# ALLPRINT-CAPBOARD-677512-MCU.net
KiCad netlist of a schematic drawn in Altium Designer
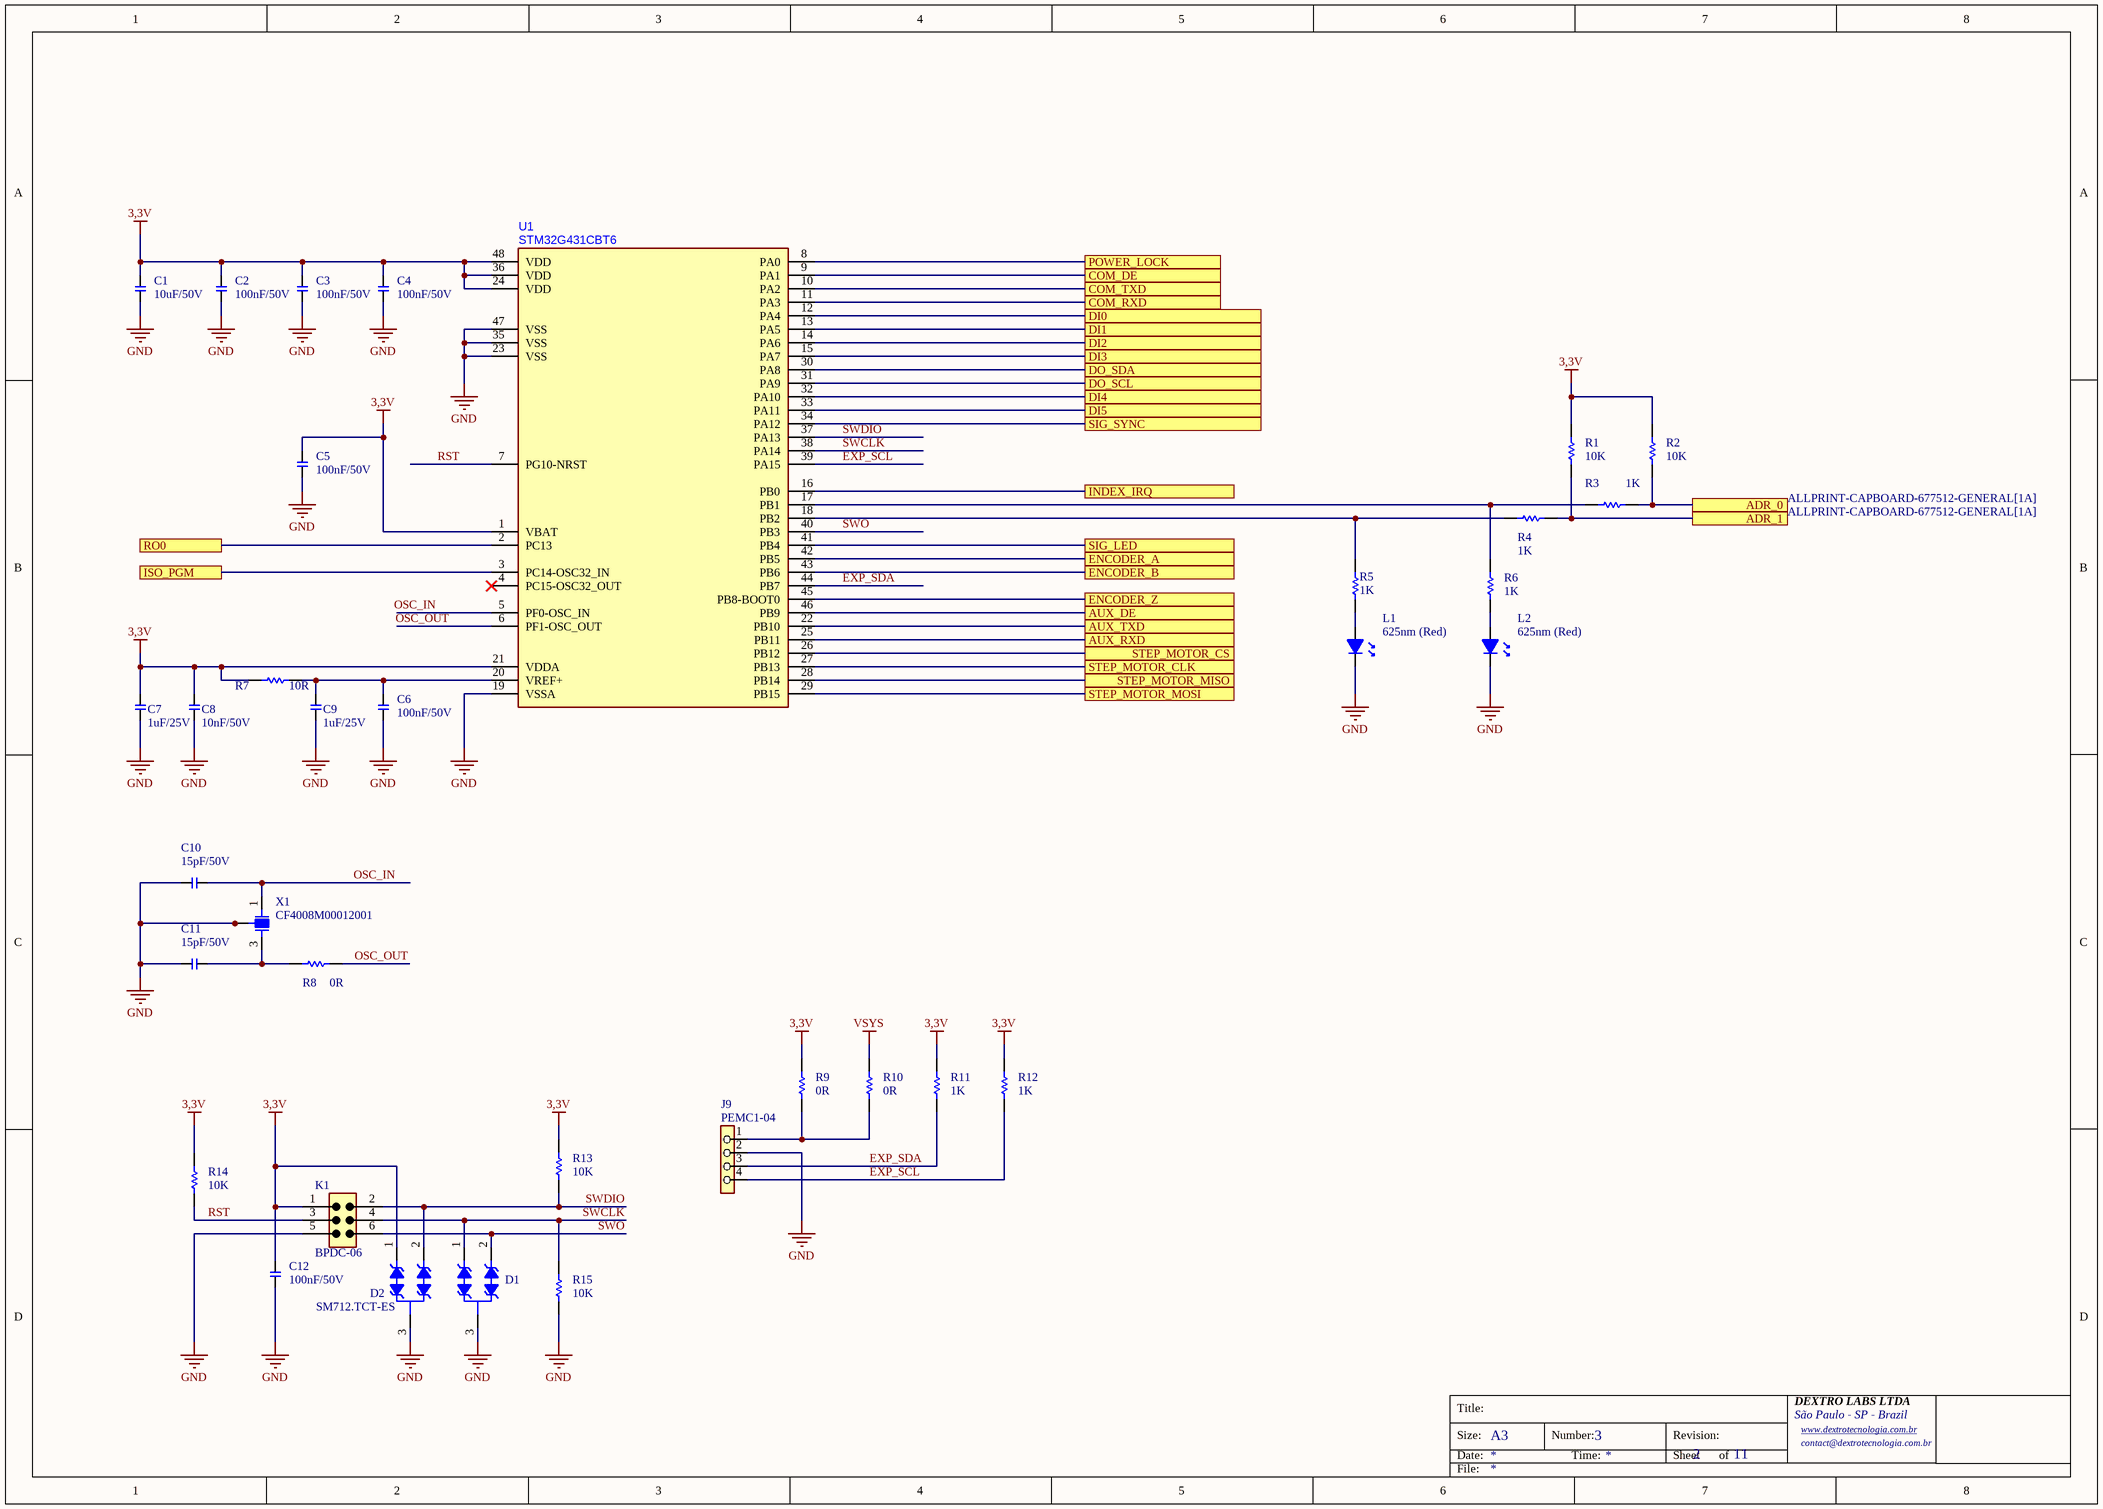
[diagram p0: ALLPRINT-CAPBOARD-677512-MCU.SchDoc]

(export (version "E")
  (design (tool "Eeschema 10.0.6"))
  (components
    (comp (ref "C1")
      (value "10uF/50V")
      (footprint "CAP-0805")
      (description "50V 10uF X5R ±10% 1206 Multilayer Ceramic Capacitors MLCC - SMD/SMT ROHS")
      (libsource (lib "dextro-labs") (part "CAP-10uF/50V-0805-X5R-MLCC"))
    )
    (comp (ref "C2")
      (value "100nF/50V")
      (footprint "CAP-0603")
      (description "50V 100nF X7R ±10% 0603 Multilayer Ceramic Capacitors MLCC - SMD/SMT ROHS")
      (libsource (lib "dextro-labs") (part "CAP-100nF/50V-0603-X7R-MLCC"))
    )
    (comp (ref "C3")
      (value "100nF/50V")
      (footprint "CAP-0603")
      (description "50V 100nF X7R ±10% 0603 Multilayer Ceramic Capacitors MLCC - SMD/SMT ROHS")
      (libsource (lib "dextro-labs") (part "CAP-100nF/50V-0603-X7R-MLCC"))
    )
    (comp (ref "C4")
      (value "100nF/50V")
      (footprint "CAP-0603")
      (description "50V 100nF X7R ±10% 0603 Multilayer Ceramic Capacitors MLCC - SMD/SMT ROHS")
      (libsource (lib "dextro-labs") (part "CAP-100nF/50V-0603-X7R-MLCC"))
    )
    (comp (ref "C5")
      (value "100nF/50V")
      (footprint "CAP-0603")
      (description "50V 100nF X7R ±10% 0603 Multilayer Ceramic Capacitors MLCC - SMD/SMT ROHS")
      (libsource (lib "dextro-labs") (part "CAP-100nF/50V-0603-X7R-MLCC"))
    )
    (comp (ref "C6")
      (value "100nF/50V")
      (footprint "CAP-0603")
      (description "50V 100nF X7R ±10% 0603 Multilayer Ceramic Capacitors MLCC - SMD/SMT ROHS")
      (libsource (lib "dextro-labs") (part "CAP-100nF/50V-0603-X7R-MLCC"))
    )
    (comp (ref "C7")
      (value "1uF/25V")
      (footprint "CAP-0603")
      (description "25V 1uF X7R ±10% 0603 Multilayer Ceramic Capacitors MLCC - SMD/SMT ROHS")
      (libsource (lib "dextro-labs") (part "CAP-1uF/25V-0603-X7R-MLCC"))
    )
    (comp (ref "C8")
      (value "10nF/50V")
      (footprint "CAP-0603")
      (description "50V 10nF X7R ±10% 0603 Multilayer Ceramic Capacitors MLCC - SMD/SMT ROHS")
      (libsource (lib "dextro-labs") (part "CAP-10nF/50V-0603-X7R-MLCC"))
    )
    (comp (ref "C9")
      (value "1uF/25V")
      (footprint "CAP-0603")
      (description "25V 1uF X7R ±10% 0603 Multilayer Ceramic Capacitors MLCC - SMD/SMT ROHS")
      (libsource (lib "dextro-labs") (part "CAP-1uF/25V-0603-X7R-MLCC"))
    )
    (comp (ref "C10")
      (value "15pF/50V")
      (footprint "CAP-0603")
      (description "50V 15pF NP0 ±5% 0603 Ceramic Capacitors RoHS")
      (libsource (lib "dextro-labs") (part "CAP-15pF/50V-0603-NP0-MLCC"))
    )
    (comp (ref "C11")
      (value "15pF/50V")
      (footprint "CAP-0603")
      (description "50V 15pF NP0 ±5% 0603 Ceramic Capacitors RoHS")
      (libsource (lib "dextro-labs") (part "CAP-15pF/50V-0603-NP0-MLCC"))
    )
    (comp (ref "C12")
      (value "100nF/50V")
      (footprint "CAP-0603")
      (description "50V 100nF X7R ±10% 0603 Multilayer Ceramic Capacitors MLCC - SMD/SMT ROHS")
      (libsource (lib "dextro-labs") (part "CAP-100nF/50V-0603-X7R-MLCC"))
    )
    (comp (ref "D1")
      (value "SM712.TCT-ES")
      (footprint "SOT23-3")
      (description "400W@8/20us Bidirectional SOT-23 ESD and Surge Protection (TVS/ESD) ROHS")
      (libsource (lib "dextro-labs") (part "SM712.TCT-ES"))
    )
    (comp (ref "D2")
      (value "SM712.TCT-ES")
      (footprint "SOT23-3")
      (description "400W@8/20us Bidirectional SOT-23 ESD and Surge Protection (TVS/ESD) ROHS")
      (libsource (lib "dextro-labs") (part "SM712.TCT-ES"))
    )
    (comp (ref "J9")
      (value "PEMC1-04")
      (footprint "PEMC1-04")
      (description "CONECTOR PASSO 2,5mm\r\n250VCA\r\n3A\r\n10mOHMS")
      (libsource (lib "dextro-labs") (part "PEMC1-04"))
    )
    (comp (ref "K1")
      (value "BPDC-06")
      (footprint "BPDC-06")
      (description "BARRA DE PINOS DUPLA 2,54mm 6 VIAS 180º")
      (libsource (lib "dextro-labs") (part "BPDC-06"))
    )
    (comp (ref "L1")
      (value "YLED0603R")
      (footprint "LED-SMD-0603")
      (description "25mA 120mcd 620nm~625nm Red 1.8V~2.4V 0603 LED Indication - Discrete RoHS")
      (fields (field (name "WAVELENGTH") "625nm (Red)"))
      (libsource (lib "dextro-labs") (part "D-LED-SMD-PKG@0603-RED"))
    )
    (comp (ref "L2")
      (value "YLED0603R")
      (footprint "LED-SMD-0603")
      (description "25mA 120mcd 620nm~625nm Red 1.8V~2.4V 0603 LED Indication - Discrete RoHS")
      (fields (field (name "WAVELENGTH") "625nm (Red)"))
      (libsource (lib "dextro-labs") (part "D-LED-SMD-PKG@0603-RED"))
    )
    (comp (ref "R1")
      (value "10K")
      (footprint "RES-0603")
      (description "100mW Thick Film Resistor 75V ±100ppm/℃ ±1% 10kΩ 0603 Chip Resistor - Surface Mount ROHS")
      (libsource (lib "dextro-labs") (part "RES-10K-1%-100mW-0603"))
    )
    (comp (ref "R2")
      (value "10K")
      (footprint "RES-0603")
      (description "100mW Thick Film Resistor 75V ±100ppm/℃ ±1% 10kΩ 0603 Chip Resistor - Surface Mount ROHS")
      (libsource (lib "dextro-labs") (part "RES-10K-1%-100mW-0603"))
    )
    (comp (ref "R3")
      (value "1K")
      (footprint "RES-0603")
      (description "100mW Thick Film Resistor 75V ±100ppm/℃ ±1% 1kΩ 0603 Chip Resistor - Surface Mount ROHS")
      (libsource (lib "dextro-labs") (part "RES-1K-1%-100mW-0603"))
    )
    (comp (ref "R4")
      (value "1K")
      (footprint "RES-0603")
      (description "100mW Thick Film Resistor 75V ±100ppm/℃ ±1% 1kΩ 0603 Chip Resistor - Surface Mount ROHS")
      (libsource (lib "dextro-labs") (part "RES-1K-1%-100mW-0603"))
    )
    (comp (ref "R5")
      (value "1K")
      (footprint "RES-0603")
      (description "100mW Thick Film Resistor 75V ±100ppm/℃ ±1% 1kΩ 0603 Chip Resistor - Surface Mount ROHS")
      (libsource (lib "dextro-labs") (part "RES-1K-1%-100mW-0603"))
    )
    (comp (ref "R6")
      (value "1K")
      (footprint "RES-0603")
      (description "100mW Thick Film Resistor 75V ±100ppm/℃ ±1% 1kΩ 0603 Chip Resistor - Surface Mount ROHS")
      (libsource (lib "dextro-labs") (part "RES-1K-1%-100mW-0603"))
    )
    (comp (ref "R7")
      (value "10R")
      (footprint "RES-0603")
      (description "100mW Thick Film Resistor 75V ±1% ±400ppm/℃ 10Ω 0603 Chip Resistor - Surface Mount ROHS")
      (libsource (lib "dextro-labs") (part "RES-10R-1%-100mW-0603"))
    )
    (comp (ref "R8")
      (value "0R")
      (footprint "RES-0603")
      (description "100mW 0Ω 75V Thick Film Resistor ±5% 0603 Chip Resistor - Surface Mount RoHS")
      (libsource (lib "dextro-labs") (part "RES-0R-1%-100mW-0603"))
    )
    (comp (ref "R9")
      (value "0R")
      (footprint "RES-0805")
      (description "100mW Thick Film Resistor 75V ±100ppm/℃ ±1% 0R Chip Resistor - Surface Mount ROHS")
      (libsource (lib "dextro-labs") (part "RES-0R-1%-125mW-0805"))
    )
    (comp (ref "R10")
      (value "0R")
      (footprint "RES-0805")
      (description "100mW Thick Film Resistor 75V ±100ppm/℃ ±1% 0R Chip Resistor - Surface Mount ROHS")
      (libsource (lib "dextro-labs") (part "RES-0R-1%-125mW-0805"))
    )
    (comp (ref "R11")
      (value "1K")
      (footprint "RES-0603")
      (description "100mW Thick Film Resistor 75V ±100ppm/℃ ±1% 1kΩ 0603 Chip Resistor - Surface Mount ROHS")
      (libsource (lib "dextro-labs") (part "RES-1K-1%-100mW-0603"))
    )
    (comp (ref "R12")
      (value "1K")
      (footprint "RES-0603")
      (description "100mW Thick Film Resistor 75V ±100ppm/℃ ±1% 1kΩ 0603 Chip Resistor - Surface Mount ROHS")
      (libsource (lib "dextro-labs") (part "RES-1K-1%-100mW-0603"))
    )
    (comp (ref "R13")
      (value "10K")
      (footprint "RES-0603")
      (description "100mW Thick Film Resistor 75V ±100ppm/℃ ±1% 10kΩ 0603 Chip Resistor - Surface Mount ROHS")
      (libsource (lib "dextro-labs") (part "RES-10K-1%-100mW-0603"))
    )
    (comp (ref "R14")
      (value "10K")
      (footprint "RES-0603")
      (description "100mW Thick Film Resistor 75V ±100ppm/℃ ±1% 10kΩ 0603 Chip Resistor - Surface Mount ROHS")
      (libsource (lib "dextro-labs") (part "RES-10K-1%-100mW-0603"))
    )
    (comp (ref "R15")
      (value "10K")
      (footprint "RES-0603")
      (description "100mW Thick Film Resistor 75V ±100ppm/℃ ±1% 10kΩ 0603 Chip Resistor - Surface Mount ROHS")
      (libsource (lib "dextro-labs") (part "RES-10K-1%-100mW-0603"))
    )
    (comp (ref "U1")
      (value "STM32G431CBT6")
      (footprint "LQFP-48_L7.0-W7.0-P0.50-LS9.0-BL")
      (fields (field (name "MANUFACTURER") "ST(意法半导体)"))
      (libsource (lib "dextro-labs") (part "STM32G431CBT6"))
    )
    (comp (ref "X1")
      (value "CF4008M00012001")
      (footprint "TAXM8M4RDBCCT2T")
      (description "Crystal Oscillator 12pF SMD3225-4P Crystals RoHS")
      (libsource (lib "dextro-labs") (part "XTAL-8MHZ-3225-SMD"))
    )
  )
  (nets
    (net (code "1") (name "/ADR_0") (class "Default")
      (node (ref "R2") (pin "1") (pinfunction "1_1") (pintype "passive"))
      (node (ref "R3") (pin "2") (pinfunction "2_2") (pintype "passive"))
    )
    (net (code "2") (name "/ADR_1") (class "Default")
      (node (ref "R1") (pin "1") (pinfunction "1_1") (pintype "passive"))
      (node (ref "R4") (pin "2") (pinfunction "2_2") (pintype "passive"))
    )
    (net (code "3") (name "/AUX_DE") (class "Default")
      (node (ref "U1") (pin "46") (pinfunction "PB9_46") (pintype "passive"))
    )
    (net (code "4") (name "/AUX_RXD") (class "Default")
      (node (ref "U1") (pin "25") (pinfunction "PB11_25") (pintype "passive"))
    )
    (net (code "5") (name "/AUX_TXD") (class "Default")
      (node (ref "U1") (pin "22") (pinfunction "PB10_22") (pintype "passive"))
    )
    (net (code "6") (name "/COM_DE") (class "Default")
      (node (ref "U1") (pin "9") (pinfunction "PA1_9") (pintype "passive"))
    )
    (net (code "7") (name "/COM_RXD") (class "Default")
      (node (ref "U1") (pin "11") (pinfunction "PA3_11") (pintype "passive"))
    )
    (net (code "8") (name "/COM_TXD") (class "Default")
      (node (ref "U1") (pin "10") (pinfunction "PA2_10") (pintype "passive"))
    )
    (net (code "9") (name "/DI0") (class "Default")
      (node (ref "U1") (pin "12") (pinfunction "PA4_12") (pintype "passive"))
    )
    (net (code "10") (name "/DI1") (class "Default")
      (node (ref "U1") (pin "13") (pinfunction "PA5_13") (pintype "passive"))
    )
    (net (code "11") (name "/DI2") (class "Default")
      (node (ref "U1") (pin "14") (pinfunction "PA6_14") (pintype "passive"))
    )
    (net (code "12") (name "/DI3") (class "Default")
      (node (ref "U1") (pin "15") (pinfunction "PA7_15") (pintype "passive"))
    )
    (net (code "13") (name "/DI4") (class "Default")
      (node (ref "U1") (pin "32") (pinfunction "PA10_32") (pintype "passive"))
    )
    (net (code "14") (name "/DI5") (class "Default")
      (node (ref "U1") (pin "33") (pinfunction "PA11_33") (pintype "passive"))
    )
    (net (code "15") (name "/DO_SCL") (class "Default")
      (node (ref "U1") (pin "31") (pinfunction "PA9_31") (pintype "passive"))
    )
    (net (code "16") (name "/DO_SDA") (class "Default")
      (node (ref "U1") (pin "30") (pinfunction "PA8_30") (pintype "passive"))
    )
    (net (code "17") (name "/ENCODER_A") (class "Default")
      (node (ref "U1") (pin "42") (pinfunction "PB5_42") (pintype "passive"))
    )
    (net (code "18") (name "/ENCODER_B") (class "Default")
      (node (ref "U1") (pin "43") (pinfunction "PB6_43") (pintype "passive"))
    )
    (net (code "19") (name "/ENCODER_Z") (class "Default")
      (node (ref "U1") (pin "45") (pinfunction "PB8-BOOT0_45") (pintype "passive"))
    )
    (net (code "20") (name "/EXP_SCL") (class "Default")
      (node (ref "J9") (pin "4") (pinfunction "4_4") (pintype "passive"))
      (node (ref "R12") (pin "1") (pinfunction "1_1") (pintype "passive"))
      (node (ref "U1") (pin "39") (pinfunction "PA15_39") (pintype "passive"))
    )
    (net (code "21") (name "/EXP_SDA") (class "Default")
      (node (ref "J9") (pin "3") (pinfunction "3_3") (pintype "passive"))
      (node (ref "R11") (pin "1") (pinfunction "1_1") (pintype "passive"))
      (node (ref "U1") (pin "44") (pinfunction "PB7_44") (pintype "passive"))
    )
    (net (code "22") (name "/INDEX_IRQ") (class "Default")
      (node (ref "U1") (pin "16") (pinfunction "PB0_16") (pintype "passive"))
    )
    (net (code "23") (name "/ISO_PGM") (class "Default")
      (node (ref "U1") (pin "3") (pinfunction "PC14-OSC32_IN_3") (pintype "passive"))
    )
    (net (code "24") (name "/OSC_IN") (class "Default")
      (node (ref "C10") (pin "2") (pinfunction "2_2") (pintype "passive"))
      (node (ref "U1") (pin "5") (pinfunction "PF0-OSC_IN_5") (pintype "passive"))
      (node (ref "X1") (pin "1") (pinfunction "1_1") (pintype "passive"))
    )
    (net (code "25") (name "/OSC_OUT") (class "Default")
      (node (ref "R8") (pin "2") (pinfunction "2_2") (pintype "passive"))
      (node (ref "U1") (pin "6") (pinfunction "PF1-OSC_OUT_6") (pintype "passive"))
    )
    (net (code "26") (name "/POWER_LOCK") (class "Default")
      (node (ref "U1") (pin "8") (pinfunction "PA0_8") (pintype "passive"))
    )
    (net (code "27") (name "/RO0") (class "Default")
      (node (ref "U1") (pin "2") (pinfunction "PC13_2") (pintype "passive"))
    )
    (net (code "28") (name "/RST") (class "Default")
      (node (ref "K1") (pin "3") (pinfunction "3_3") (pintype "passive"))
      (node (ref "R14") (pin "1") (pinfunction "1_1") (pintype "passive"))
      (node (ref "U1") (pin "7") (pinfunction "PG10-NRST_7") (pintype "passive"))
    )
    (net (code "29") (name "/SIG_LED") (class "Default")
      (node (ref "U1") (pin "41") (pinfunction "PB4_41") (pintype "passive"))
    )
    (net (code "30") (name "/SIG_SYNC") (class "Default")
      (node (ref "U1") (pin "34") (pinfunction "PA12_34") (pintype "passive"))
    )
    (net (code "31") (name "/STEP_MOTOR_CLK") (class "Default")
      (node (ref "U1") (pin "27") (pinfunction "PB13_27") (pintype "passive"))
    )
    (net (code "32") (name "/STEP_MOTOR_CS") (class "Default")
      (node (ref "U1") (pin "26") (pinfunction "PB12_26") (pintype "passive"))
    )
    (net (code "33") (name "/STEP_MOTOR_MISO") (class "Default")
      (node (ref "U1") (pin "28") (pinfunction "PB14_28") (pintype "passive"))
    )
    (net (code "34") (name "/STEP_MOTOR_MOSI") (class "Default")
      (node (ref "U1") (pin "29") (pinfunction "PB15_29") (pintype "passive"))
    )
    (net (code "35") (name "/SWCLK") (class "Default")
      (node (ref "D1") (pin "1") (pinfunction "A1_1") (pintype "passive"))
      (node (ref "K1") (pin "4") (pinfunction "4_4") (pintype "passive"))
      (node (ref "R15") (pin "2") (pinfunction "2_2") (pintype "passive"))
      (node (ref "U1") (pin "38") (pinfunction "PA14_38") (pintype "passive"))
    )
    (net (code "36") (name "/SWDIO") (class "Default")
      (node (ref "D2") (pin "2") (pinfunction "A2_2") (pintype "passive"))
      (node (ref "K1") (pin "2") (pinfunction "2_2") (pintype "passive"))
      (node (ref "R13") (pin "1") (pinfunction "1_1") (pintype "passive"))
      (node (ref "U1") (pin "37") (pinfunction "PA13_37") (pintype "passive"))
    )
    (net (code "37") (name "/SWO") (class "Default")
      (node (ref "D1") (pin "2") (pinfunction "A2_2") (pintype "passive"))
      (node (ref "K1") (pin "6") (pinfunction "6_6") (pintype "passive"))
      (node (ref "U1") (pin "40") (pinfunction "PB3_40") (pintype "passive"))
    )
    (net (code "38") (name "3,3V") (class "Default")
      (node (ref "C1") (pin "2") (pinfunction "2_2") (pintype "passive"))
      (node (ref "C12") (pin "2") (pinfunction "2_2") (pintype "passive"))
      (node (ref "C2") (pin "2") (pinfunction "2_2") (pintype "passive"))
      (node (ref "C3") (pin "2") (pinfunction "2_2") (pintype "passive"))
      (node (ref "C4") (pin "2") (pinfunction "2_2") (pintype "passive"))
      (node (ref "C5") (pin "2") (pinfunction "2_2") (pintype "passive"))
      (node (ref "C7") (pin "2") (pinfunction "2_2") (pintype "passive"))
      (node (ref "C8") (pin "2") (pinfunction "2_2") (pintype "passive"))
      (node (ref "D2") (pin "1") (pinfunction "A1_1") (pintype "passive"))
      (node (ref "K1") (pin "1") (pinfunction "1_1") (pintype "passive"))
      (node (ref "R1") (pin "2") (pinfunction "2_2") (pintype "passive"))
      (node (ref "R11") (pin "2") (pinfunction "2_2") (pintype "passive"))
      (node (ref "R12") (pin "2") (pinfunction "2_2") (pintype "passive"))
      (node (ref "R13") (pin "2") (pinfunction "2_2") (pintype "passive"))
      (node (ref "R14") (pin "2") (pinfunction "2_2") (pintype "passive"))
      (node (ref "R2") (pin "2") (pinfunction "2_2") (pintype "passive"))
      (node (ref "R7") (pin "1") (pinfunction "1_1") (pintype "passive"))
      (node (ref "R9") (pin "2") (pinfunction "2_2") (pintype "passive"))
      (node (ref "U1") (pin "1") (pinfunction "VBAT_1") (pintype "passive"))
      (node (ref "U1") (pin "21") (pinfunction "VDDA_21") (pintype "passive"))
      (node (ref "U1") (pin "24") (pinfunction "VDD_24") (pintype "passive"))
      (node (ref "U1") (pin "36") (pinfunction "VDD_36") (pintype "passive"))
      (node (ref "U1") (pin "48") (pinfunction "VDD_48") (pintype "passive"))
    )
    (net (code "39") (name "GND") (class "Default")
      (node (ref "C1") (pin "1") (pinfunction "1_1") (pintype "passive"))
      (node (ref "C10") (pin "1") (pinfunction "1_1") (pintype "passive"))
      (node (ref "C11") (pin "1") (pinfunction "1_1") (pintype "passive"))
      (node (ref "C12") (pin "1") (pinfunction "1_1") (pintype "passive"))
      (node (ref "C2") (pin "1") (pinfunction "1_1") (pintype "passive"))
      (node (ref "C3") (pin "1") (pinfunction "1_1") (pintype "passive"))
      (node (ref "C4") (pin "1") (pinfunction "1_1") (pintype "passive"))
      (node (ref "C5") (pin "1") (pinfunction "1_1") (pintype "passive"))
      (node (ref "C6") (pin "1") (pinfunction "1_1") (pintype "passive"))
      (node (ref "C7") (pin "1") (pinfunction "1_1") (pintype "passive"))
      (node (ref "C8") (pin "1") (pinfunction "1_1") (pintype "passive"))
      (node (ref "C9") (pin "1") (pinfunction "1_1") (pintype "passive"))
      (node (ref "D1") (pin "3") (pinfunction "K_3") (pintype "passive"))
      (node (ref "D2") (pin "3") (pinfunction "K_3") (pintype "passive"))
      (node (ref "J9") (pin "2") (pinfunction "2_2") (pintype "passive"))
      (node (ref "K1") (pin "5") (pinfunction "5_5") (pintype "passive"))
      (node (ref "L1") (pin "1") (pinfunction "K_1") (pintype "passive"))
      (node (ref "L2") (pin "1") (pinfunction "K_1") (pintype "passive"))
      (node (ref "R15") (pin "1") (pinfunction "1_1") (pintype "passive"))
      (node (ref "U1") (pin "19") (pinfunction "VSSA_19") (pintype "passive"))
      (node (ref "U1") (pin "23") (pinfunction "VSS_23") (pintype "passive"))
      (node (ref "U1") (pin "35") (pinfunction "VSS_35") (pintype "passive"))
      (node (ref "U1") (pin "47") (pinfunction "VSS_47") (pintype "passive"))
      (node (ref "X1") (pin "2") (pinfunction "2_2") (pintype "passive"))
      (node (ref "X1") (pin "4") (pinfunction "4_4") (pintype "passive"))
    )
    (net (code "40") (name "Net-(C11-Pad2)") (class "Default")
      (node (ref "C11") (pin "2") (pinfunction "2_2") (pintype "passive"))
      (node (ref "R8") (pin "1") (pinfunction "1_1") (pintype "passive"))
      (node (ref "X1") (pin "3") (pinfunction "3_3") (pintype "passive"))
    )
    (net (code "41") (name "Net-(J9-Pad1)") (class "Default")
      (node (ref "J9") (pin "1") (pinfunction "1_1") (pintype "passive"))
      (node (ref "R10") (pin "1") (pinfunction "1_1") (pintype "passive"))
      (node (ref "R9") (pin "1") (pinfunction "1_1") (pintype "passive"))
    )
    (net (code "42") (name "Net-(L1-A)") (class "Default")
      (node (ref "L1") (pin "2") (pinfunction "A_2") (pintype "passive"))
      (node (ref "R5") (pin "2") (pinfunction "2_2") (pintype "passive"))
    )
    (net (code "43") (name "Net-(L2-A)") (class "Default")
      (node (ref "L2") (pin "2") (pinfunction "A_2") (pintype "passive"))
      (node (ref "R6") (pin "1") (pinfunction "1_1") (pintype "passive"))
    )
    (net (code "44") (name "Net-(U1-PB1)") (class "Default")
      (node (ref "R3") (pin "1") (pinfunction "1_1") (pintype "passive"))
      (node (ref "R6") (pin "2") (pinfunction "2_2") (pintype "passive"))
      (node (ref "U1") (pin "17") (pinfunction "PB1_17") (pintype "passive"))
    )
    (net (code "45") (name "Net-(U1-PB2)") (class "Default")
      (node (ref "R4") (pin "1") (pinfunction "1_1") (pintype "passive"))
      (node (ref "R5") (pin "1") (pinfunction "1_1") (pintype "passive"))
      (node (ref "U1") (pin "18") (pinfunction "PB2_18") (pintype "passive"))
    )
    (net (code "46") (name "Net-(U1-VREF+)") (class "Default")
      (node (ref "C6") (pin "2") (pinfunction "2_2") (pintype "passive"))
      (node (ref "C9") (pin "2") (pinfunction "2_2") (pintype "passive"))
      (node (ref "R7") (pin "2") (pinfunction "2_2") (pintype "passive"))
      (node (ref "U1") (pin "20") (pinfunction "VREF+_20") (pintype "passive"))
    )
    (net (code "47") (name "VSYS") (class "Default")
      (node (ref "R10") (pin "2") (pinfunction "2_2") (pintype "passive"))
    )
    (net (code "48") (name "unconnected-(U1-PC15-OSC32_OUT-Pad4)") (class "Default")
      (node (ref "U1") (pin "4") (pinfunction "PC15-OSC32_OUT_4") (pintype "passive+no_connect"))
    )
  )
)
